# 11_VIDEO_PORT.net
KiCad netlist of a schematic drawn in Altium Designer
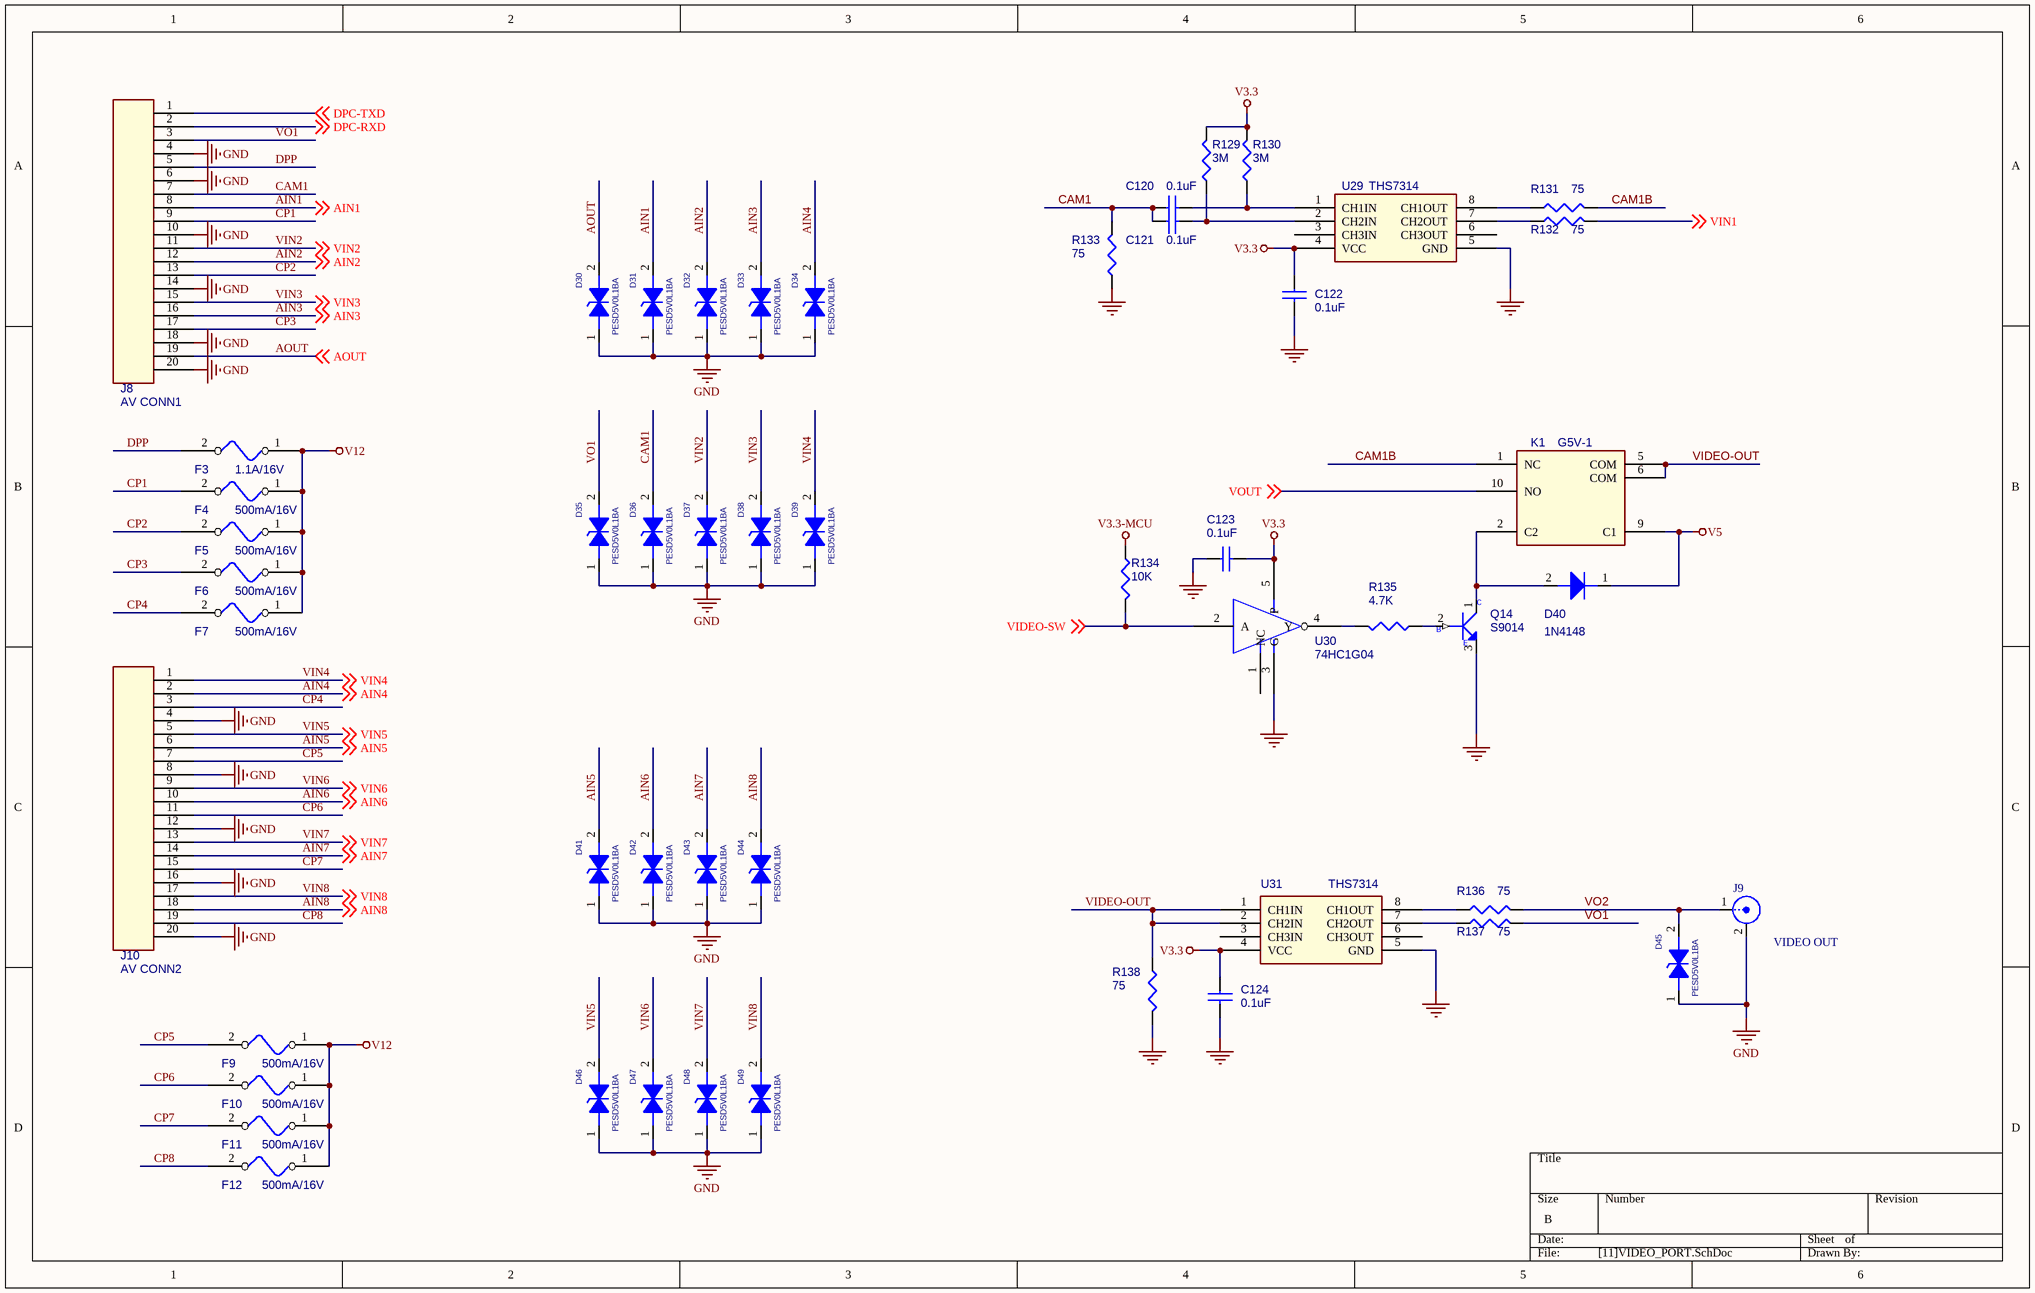
[diagram p0: [11]VIDEO_PORT.SchDoc]

(export (version "E")
  (design (tool "Eeschema 10.0.6"))
  (components
    (comp (ref "C120") (value "0.1uF") (libsource (lib "*") (part "CAP")))
    (comp (ref "C121") (value "0.1uF") (libsource (lib "*") (part "CAP")))
    (comp (ref "C122") (value "0.1uF") (libsource (lib "*") (part "CAP")))
    (comp (ref "C123")
      (value "0.1uF")
      (fields (field (name "PART NUMBER") "SE132225K8L"))
      (libsource (lib "*") (part "P_CAP NP"))
    )
    (comp (ref "C124") (value "0.1uF") (libsource (lib "*") (part "CAP")))
    (comp (ref "D30") (value "PESD5V0L1BA") (libsource (lib "*") (part "PESD")))
    (comp (ref "D31") (value "PESD5V0L1BA") (libsource (lib "*") (part "PESD")))
    (comp (ref "D32") (value "PESD5V0L1BA") (libsource (lib "*") (part "PESD")))
    (comp (ref "D33") (value "PESD5V0L1BA") (libsource (lib "*") (part "PESD")))
    (comp (ref "D34") (value "PESD5V0L1BA") (libsource (lib "*") (part "PESD")))
    (comp (ref "D35") (value "PESD5V0L1BA") (libsource (lib "*") (part "PESD")))
    (comp (ref "D36") (value "PESD5V0L1BA") (libsource (lib "*") (part "PESD")))
    (comp (ref "D37") (value "PESD5V0L1BA") (libsource (lib "*") (part "PESD")))
    (comp (ref "D38") (value "PESD5V0L1BA") (libsource (lib "*") (part "PESD")))
    (comp (ref "D39") (value "PESD5V0L1BA") (libsource (lib "*") (part "PESD")))
    (comp (ref "D40")
      (value "1N4148")
      (footprint "MINI-MELF")
      (libsource (lib "*") (part "1N4148WS-7-F_SOD323-2"))
    )
    (comp (ref "D41") (value "PESD5V0L1BA") (libsource (lib "*") (part "PESD")))
    (comp (ref "D42") (value "PESD5V0L1BA") (libsource (lib "*") (part "PESD")))
    (comp (ref "D43") (value "PESD5V0L1BA") (libsource (lib "*") (part "PESD")))
    (comp (ref "D44") (value "PESD5V0L1BA") (libsource (lib "*") (part "PESD")))
    (comp (ref "D45") (value "PESD5V0L1BA") (libsource (lib "*") (part "PESD")))
    (comp (ref "D46") (value "PESD5V0L1BA") (libsource (lib "*") (part "PESD")))
    (comp (ref "D47") (value "PESD5V0L1BA") (libsource (lib "*") (part "PESD")))
    (comp (ref "D48") (value "PESD5V0L1BA") (libsource (lib "*") (part "PESD")))
    (comp (ref "D49") (value "PESD5V0L1BA") (libsource (lib "*") (part "PESD")))
    (comp (ref "F3") (value "1.1A/16V") (libsource (lib "*") (part "2A_32VDC_0467-002")))
    (comp (ref "F4") (value "500mA/16V") (libsource (lib "*") (part "2A_32VDC_0467-002")))
    (comp (ref "F5") (value "500mA/16V") (libsource (lib "*") (part "2A_32VDC_0467-002")))
    (comp (ref "F6") (value "500mA/16V") (libsource (lib "*") (part "2A_32VDC_0467-002")))
    (comp (ref "F7") (value "500mA/16V") (libsource (lib "*") (part "2A_32VDC_0467-002")))
    (comp (ref "F9") (value "500mA/16V") (libsource (lib "*") (part "2A_32VDC_0467-002")))
    (comp (ref "F10") (value "500mA/16V") (libsource (lib "*") (part "2A_32VDC_0467-002")))
    (comp (ref "F11") (value "500mA/16V") (libsource (lib "*") (part "2A_32VDC_0467-002")))
    (comp (ref "F12") (value "500mA/16V") (libsource (lib "*") (part "2A_32VDC_0467-002")))
    (comp (ref "J8") (value "AV CONN1") (libsource (lib "*") (part "CON20")))
    (comp (ref "J9")
      (value "VIDEO OUT")
      (footprint "RCA2")
      (description "BNC Elbow Connector")
      (fields (field (name "PUBLISHER") "Altium Limited"))
      (libsource (lib "Miscellaneous Connectors") (part "BNC"))
    )
    (comp (ref "J10") (value "AV CONN2") (libsource (lib "*") (part "CON20")))
    (comp (ref "K1") (value "G5V-1") (libsource (lib "*") (part "G5V-1_0")))
    (comp (ref "Q14")
      (value "S9014")
      (footprint "NPN")
      (fields (field (name "PART NUMBER") "SB039040000"))
      (libsource (lib "*") (part "MMBT3904_NL_SOT23-3"))
    )
    (comp (ref "R129")
      (value "3M")
      (fields (field (name "PART NUMBER") "SD02810028L"))
      (libsource (lib "*") (part "R"))
    )
    (comp (ref "R130")
      (value "3M")
      (fields (field (name "PART NUMBER") "SD02810028L"))
      (libsource (lib "*") (part "R"))
    )
    (comp (ref "R131")
      (value "75")
      (fields (field (name "PART NUMBER") "SD02810028L"))
      (libsource (lib "*") (part "R"))
    )
    (comp (ref "R132")
      (value "75")
      (fields (field (name "PART NUMBER") "SD02810028L"))
      (libsource (lib "*") (part "R"))
    )
    (comp (ref "R133")
      (value "75")
      (fields (field (name "PART NUMBER") "SD02810028L"))
      (libsource (lib "*") (part "R"))
    )
    (comp (ref "R134")
      (value "10K")
      (fields (field (name "PART NUMBER") "SD02810028L"))
      (libsource (lib "*") (part "R"))
    )
    (comp (ref "R135")
      (value "4.7K")
      (fields (field (name "PART NUMBER") "SD02810028L"))
      (libsource (lib "*") (part "R"))
    )
    (comp (ref "R136")
      (value "75")
      (fields (field (name "PART NUMBER") "SD02810028L"))
      (libsource (lib "*") (part "R"))
    )
    (comp (ref "R137")
      (value "75")
      (fields (field (name "PART NUMBER") "SD02810028L"))
      (libsource (lib "*") (part "R"))
    )
    (comp (ref "R138")
      (value "75")
      (fields (field (name "PART NUMBER") "SD02810028L"))
      (libsource (lib "*") (part "R"))
    )
    (comp (ref "U29") (value "THS7314") (libsource (lib "*") (part "THS7314")))
    (comp (ref "U30") (value "74HC1G04") (libsource (lib "*") (part "74LVC1G04GW_SOT353-5")))
    (comp (ref "U31") (value "THS7314") (libsource (lib "*") (part "THS7314")))
  )
  (nets
    (net (code "1") (name "/CAM1") (class "Default")
      (node (ref "C120") (pin "1") (pinfunction "1_1") (pintype "passive"))
      (node (ref "C121") (pin "1") (pinfunction "1_1") (pintype "passive"))
      (node (ref "D36") (pin "2") (pinfunction "2_2") (pintype "passive"))
      (node (ref "J8") (pin "7") (pinfunction "7_7") (pintype "passive"))
      (node (ref "R133") (pin "2") (pinfunction "2_2") (pintype "passive"))
    )
    (net (code "2") (name "/CAM1B") (class "Default")
      (node (ref "K1") (pin "1") (pinfunction "NC_1") (pintype "passive"))
      (node (ref "R131") (pin "2") (pinfunction "2_2") (pintype "passive"))
    )
    (net (code "3") (name "/CP1") (class "Default")
      (node (ref "F4") (pin "2") (pinfunction "2_2") (pintype "passive"))
      (node (ref "J8") (pin "9") (pinfunction "9_9") (pintype "passive"))
    )
    (net (code "4") (name "/CP2") (class "Default")
      (node (ref "F5") (pin "2") (pinfunction "2_2") (pintype "passive"))
      (node (ref "J8") (pin "13") (pinfunction "13_13") (pintype "passive"))
    )
    (net (code "5") (name "/CP3") (class "Default")
      (node (ref "F6") (pin "2") (pinfunction "2_2") (pintype "passive"))
      (node (ref "J8") (pin "17") (pinfunction "17_17") (pintype "passive"))
    )
    (net (code "6") (name "/CP4") (class "Default")
      (node (ref "F7") (pin "2") (pinfunction "2_2") (pintype "passive"))
      (node (ref "J10") (pin "3") (pinfunction "3_3") (pintype "passive"))
    )
    (net (code "7") (name "/CP5") (class "Default")
      (node (ref "F9") (pin "2") (pinfunction "2_2") (pintype "passive"))
      (node (ref "J10") (pin "7") (pinfunction "7_7") (pintype "passive"))
    )
    (net (code "8") (name "/CP6") (class "Default")
      (node (ref "F10") (pin "2") (pinfunction "2_2") (pintype "passive"))
      (node (ref "J10") (pin "11") (pinfunction "11_11") (pintype "passive"))
    )
    (net (code "9") (name "/CP7") (class "Default")
      (node (ref "F11") (pin "2") (pinfunction "2_2") (pintype "passive"))
      (node (ref "J10") (pin "15") (pinfunction "15_15") (pintype "passive"))
    )
    (net (code "10") (name "/CP8") (class "Default")
      (node (ref "F12") (pin "2") (pinfunction "2_2") (pintype "passive"))
      (node (ref "J10") (pin "19") (pinfunction "19_19") (pintype "passive"))
    )
    (net (code "11") (name "/DPP") (class "Default")
      (node (ref "F3") (pin "2") (pinfunction "2_2") (pintype "passive"))
      (node (ref "J8") (pin "5") (pinfunction "5_5") (pintype "passive"))
    )
    (net (code "12") (name "/VIDEO-OUT") (class "Default")
      (node (ref "K1") (pin "5") (pinfunction "COM_5") (pintype "power_in"))
      (node (ref "K1") (pin "6") (pinfunction "COM_6") (pintype "power_in"))
      (node (ref "R138") (pin "1") (pinfunction "1_1") (pintype "passive"))
      (node (ref "U31") (pin "1") (pinfunction "CH1IN_1") (pintype "passive"))
      (node (ref "U31") (pin "2") (pinfunction "CH2IN_2") (pintype "passive"))
    )
    (net (code "13") (name "/VO1") (class "Default")
      (node (ref "D35") (pin "2") (pinfunction "2_2") (pintype "passive"))
      (node (ref "J8") (pin "3") (pinfunction "3_3") (pintype "passive"))
      (node (ref "R137") (pin "2") (pinfunction "2_2") (pintype "passive"))
    )
    (net (code "14") (name "/VO2") (class "Default")
      (node (ref "D45") (pin "2") (pinfunction "2_2") (pintype "passive"))
      (node (ref "J9") (pin "1") (pinfunction "X_1") (pintype "passive"))
      (node (ref "R136") (pin "2") (pinfunction "2_2") (pintype "passive"))
    )
    (net (code "15") (name "AIN1") (class "Default")
      (node (ref "D31") (pin "2") (pinfunction "2_2") (pintype "passive"))
      (node (ref "J8") (pin "8") (pinfunction "8_8") (pintype "passive"))
    )
    (net (code "16") (name "AIN2") (class "Default")
      (node (ref "D32") (pin "2") (pinfunction "2_2") (pintype "passive"))
      (node (ref "J8") (pin "12") (pinfunction "12_12") (pintype "passive"))
    )
    (net (code "17") (name "AIN3") (class "Default")
      (node (ref "D33") (pin "2") (pinfunction "2_2") (pintype "passive"))
      (node (ref "J8") (pin "16") (pinfunction "16_16") (pintype "passive"))
    )
    (net (code "18") (name "AIN4") (class "Default")
      (node (ref "D34") (pin "2") (pinfunction "2_2") (pintype "passive"))
      (node (ref "J10") (pin "2") (pinfunction "2_2") (pintype "passive"))
    )
    (net (code "19") (name "AIN5") (class "Default")
      (node (ref "D41") (pin "2") (pinfunction "2_2") (pintype "passive"))
      (node (ref "J10") (pin "6") (pinfunction "6_6") (pintype "passive"))
    )
    (net (code "20") (name "AIN6") (class "Default")
      (node (ref "D42") (pin "2") (pinfunction "2_2") (pintype "passive"))
      (node (ref "J10") (pin "10") (pinfunction "10_10") (pintype "passive"))
    )
    (net (code "21") (name "AIN7") (class "Default")
      (node (ref "D43") (pin "2") (pinfunction "2_2") (pintype "passive"))
      (node (ref "J10") (pin "14") (pinfunction "14_14") (pintype "passive"))
    )
    (net (code "22") (name "AIN8") (class "Default")
      (node (ref "D44") (pin "2") (pinfunction "2_2") (pintype "passive"))
      (node (ref "J10") (pin "18") (pinfunction "18_18") (pintype "passive"))
    )
    (net (code "23") (name "AOUT") (class "Default")
      (node (ref "D30") (pin "2") (pinfunction "2_2") (pintype "passive"))
      (node (ref "J8") (pin "19") (pinfunction "19_19") (pintype "passive"))
    )
    (net (code "24") (name "DPC-RXD") (class "Default")
      (node (ref "J8") (pin "2") (pinfunction "2_2") (pintype "passive"))
    )
    (net (code "25") (name "DPC-TXD") (class "Default")
      (node (ref "J8") (pin "1") (pinfunction "1_1") (pintype "passive"))
    )
    (net (code "26") (name "GND") (class "Default")
      (node (ref "C122") (pin "2") (pinfunction "2_2") (pintype "passive"))
      (node (ref "C123") (pin "1") (pinfunction "1_1") (pintype "passive"))
      (node (ref "C124") (pin "2") (pinfunction "2_2") (pintype "passive"))
      (node (ref "D30") (pin "1") (pinfunction "1_1") (pintype "passive"))
      (node (ref "D31") (pin "1") (pinfunction "1_1") (pintype "passive"))
      (node (ref "D32") (pin "1") (pinfunction "1_1") (pintype "passive"))
      (node (ref "D33") (pin "1") (pinfunction "1_1") (pintype "passive"))
      (node (ref "D34") (pin "1") (pinfunction "1_1") (pintype "passive"))
      (node (ref "D35") (pin "1") (pinfunction "1_1") (pintype "passive"))
      (node (ref "D36") (pin "1") (pinfunction "1_1") (pintype "passive"))
      (node (ref "D37") (pin "1") (pinfunction "1_1") (pintype "passive"))
      (node (ref "D38") (pin "1") (pinfunction "1_1") (pintype "passive"))
      (node (ref "D39") (pin "1") (pinfunction "1_1") (pintype "passive"))
      (node (ref "D41") (pin "1") (pinfunction "1_1") (pintype "passive"))
      (node (ref "D42") (pin "1") (pinfunction "1_1") (pintype "passive"))
      (node (ref "D43") (pin "1") (pinfunction "1_1") (pintype "passive"))
      (node (ref "D44") (pin "1") (pinfunction "1_1") (pintype "passive"))
      (node (ref "D45") (pin "1") (pinfunction "1_1") (pintype "passive"))
      (node (ref "D46") (pin "1") (pinfunction "1_1") (pintype "passive"))
      (node (ref "D47") (pin "1") (pinfunction "1_1") (pintype "passive"))
      (node (ref "D48") (pin "1") (pinfunction "1_1") (pintype "passive"))
      (node (ref "D49") (pin "1") (pinfunction "1_1") (pintype "passive"))
      (node (ref "J10") (pin "12") (pinfunction "12_12") (pintype "passive"))
      (node (ref "J10") (pin "16") (pinfunction "16_16") (pintype "passive"))
      (node (ref "J10") (pin "20") (pinfunction "20_20") (pintype "passive"))
      (node (ref "J10") (pin "4") (pinfunction "4_4") (pintype "passive"))
      (node (ref "J10") (pin "8") (pinfunction "8_8") (pintype "passive"))
      (node (ref "J8") (pin "10") (pinfunction "10_10") (pintype "passive"))
      (node (ref "J8") (pin "14") (pinfunction "14_14") (pintype "passive"))
      (node (ref "J8") (pin "18") (pinfunction "18_18") (pintype "passive"))
      (node (ref "J8") (pin "20") (pinfunction "20_20") (pintype "passive"))
      (node (ref "J8") (pin "4") (pinfunction "4_4") (pintype "passive"))
      (node (ref "J8") (pin "6") (pinfunction "6_6") (pintype "passive"))
      (node (ref "J9") (pin "2") (pinfunction "Y_2") (pintype "passive"))
      (node (ref "Q14") (pin "3") (pinfunction "EMITTER_3") (pintype "passive"))
      (node (ref "R133") (pin "1") (pinfunction "1_1") (pintype "passive"))
      (node (ref "R138") (pin "2") (pinfunction "2_2") (pintype "passive"))
      (node (ref "U29") (pin "5") (pinfunction "GND_5") (pintype "passive"))
      (node (ref "U30") (pin "3") (pinfunction "G_3") (pintype "passive"))
      (node (ref "U31") (pin "5") (pinfunction "GND_5") (pintype "passive"))
    )
    (net (code "27") (name "Net-(K1-C2)") (class "Default")
      (node (ref "D40") (pin "2") (pinfunction "2_2") (pintype "passive"))
      (node (ref "K1") (pin "2") (pinfunction "C2_2") (pintype "passive"))
      (node (ref "Q14") (pin "1") (pinfunction "COLLECTOR_1") (pintype "passive"))
    )
    (net (code "28") (name "Net-(Q14-BASE)") (class "Default")
      (node (ref "Q14") (pin "2") (pinfunction "BASE_2") (pintype "input"))
      (node (ref "R135") (pin "1") (pinfunction "1_1") (pintype "passive"))
    )
    (net (code "29") (name "Net-(U29-CH1IN)") (class "Default")
      (node (ref "C120") (pin "2") (pinfunction "2_2") (pintype "passive"))
      (node (ref "R130") (pin "1") (pinfunction "1_1") (pintype "passive"))
      (node (ref "U29") (pin "1") (pinfunction "CH1IN_1") (pintype "passive"))
    )
    (net (code "30") (name "Net-(U29-CH1OUT)") (class "Default")
      (node (ref "R131") (pin "1") (pinfunction "1_1") (pintype "passive"))
      (node (ref "U29") (pin "8") (pinfunction "CH1OUT_8") (pintype "passive"))
    )
    (net (code "31") (name "Net-(U29-CH2IN)") (class "Default")
      (node (ref "C121") (pin "2") (pinfunction "2_2") (pintype "passive"))
      (node (ref "R129") (pin "1") (pinfunction "1_1") (pintype "passive"))
      (node (ref "U29") (pin "2") (pinfunction "CH2IN_2") (pintype "passive"))
    )
    (net (code "32") (name "Net-(U29-CH2OUT)") (class "Default")
      (node (ref "R132") (pin "1") (pinfunction "1_1") (pintype "passive"))
      (node (ref "U29") (pin "7") (pinfunction "CH2OUT_7") (pintype "passive"))
    )
    (net (code "33") (name "Net-(U30-Y)") (class "Default")
      (node (ref "R135") (pin "2") (pinfunction "2_2") (pintype "passive"))
      (node (ref "U30") (pin "4") (pinfunction "Y_4") (pintype "passive"))
    )
    (net (code "34") (name "Net-(U31-CH1OUT)") (class "Default")
      (node (ref "R136") (pin "1") (pinfunction "1_1") (pintype "passive"))
      (node (ref "U31") (pin "8") (pinfunction "CH1OUT_8") (pintype "passive"))
    )
    (net (code "35") (name "Net-(U31-CH2OUT)") (class "Default")
      (node (ref "R137") (pin "1") (pinfunction "1_1") (pintype "passive"))
      (node (ref "U31") (pin "7") (pinfunction "CH2OUT_7") (pintype "passive"))
    )
    (net (code "36") (name "V3.3") (class "Default")
      (node (ref "C122") (pin "1") (pinfunction "1_1") (pintype "passive"))
      (node (ref "C123") (pin "2") (pinfunction "2_2") (pintype "passive"))
      (node (ref "C124") (pin "1") (pinfunction "1_1") (pintype "passive"))
      (node (ref "R129") (pin "2") (pinfunction "2_2") (pintype "passive"))
      (node (ref "R130") (pin "2") (pinfunction "2_2") (pintype "passive"))
      (node (ref "U29") (pin "4") (pinfunction "VCC_4") (pintype "passive"))
      (node (ref "U30") (pin "5") (pinfunction "P_5") (pintype "passive"))
      (node (ref "U31") (pin "4") (pinfunction "VCC_4") (pintype "passive"))
    )
    (net (code "37") (name "V3.3-MCU") (class "Default")
      (node (ref "R134") (pin "1") (pinfunction "1_1") (pintype "passive"))
    )
    (net (code "38") (name "V5") (class "Default")
      (node (ref "D40") (pin "1") (pinfunction "1_1") (pintype "passive"))
      (node (ref "K1") (pin "9") (pinfunction "C1_9") (pintype "passive"))
    )
    (net (code "39") (name "V12") (class "Default")
      (node (ref "F10") (pin "1") (pinfunction "1_1") (pintype "passive"))
      (node (ref "F11") (pin "1") (pinfunction "1_1") (pintype "passive"))
      (node (ref "F12") (pin "1") (pinfunction "1_1") (pintype "passive"))
      (node (ref "F3") (pin "1") (pinfunction "1_1") (pintype "passive"))
      (node (ref "F4") (pin "1") (pinfunction "1_1") (pintype "passive"))
      (node (ref "F5") (pin "1") (pinfunction "1_1") (pintype "passive"))
      (node (ref "F6") (pin "1") (pinfunction "1_1") (pintype "passive"))
      (node (ref "F7") (pin "1") (pinfunction "1_1") (pintype "passive"))
      (node (ref "F9") (pin "1") (pinfunction "1_1") (pintype "passive"))
    )
    (net (code "40") (name "VIDEO-SW") (class "Default")
      (node (ref "R134") (pin "2") (pinfunction "2_2") (pintype "passive"))
      (node (ref "U30") (pin "2") (pinfunction "A_2") (pintype "passive"))
    )
    (net (code "41") (name "VIN1") (class "Default")
      (node (ref "R132") (pin "2") (pinfunction "2_2") (pintype "passive"))
    )
    (net (code "42") (name "VIN2") (class "Default")
      (node (ref "D37") (pin "2") (pinfunction "2_2") (pintype "passive"))
      (node (ref "J8") (pin "11") (pinfunction "11_11") (pintype "passive"))
    )
    (net (code "43") (name "VIN3") (class "Default")
      (node (ref "D38") (pin "2") (pinfunction "2_2") (pintype "passive"))
      (node (ref "J8") (pin "15") (pinfunction "15_15") (pintype "passive"))
    )
    (net (code "44") (name "VIN4") (class "Default")
      (node (ref "D39") (pin "2") (pinfunction "2_2") (pintype "passive"))
      (node (ref "J10") (pin "1") (pinfunction "1_1") (pintype "passive"))
    )
    (net (code "45") (name "VIN5") (class "Default")
      (node (ref "D46") (pin "2") (pinfunction "2_2") (pintype "passive"))
      (node (ref "J10") (pin "5") (pinfunction "5_5") (pintype "passive"))
    )
    (net (code "46") (name "VIN6") (class "Default")
      (node (ref "D47") (pin "2") (pinfunction "2_2") (pintype "passive"))
      (node (ref "J10") (pin "9") (pinfunction "9_9") (pintype "passive"))
    )
    (net (code "47") (name "VIN7") (class "Default")
      (node (ref "D48") (pin "2") (pinfunction "2_2") (pintype "passive"))
      (node (ref "J10") (pin "13") (pinfunction "13_13") (pintype "passive"))
    )
    (net (code "48") (name "VIN8") (class "Default")
      (node (ref "D49") (pin "2") (pinfunction "2_2") (pintype "passive"))
      (node (ref "J10") (pin "17") (pinfunction "17_17") (pintype "passive"))
    )
    (net (code "49") (name "VOUT") (class "Default")
      (node (ref "K1") (pin "10") (pinfunction "NO_10") (pintype "passive"))
    )
    (net (code "50") (name "unconnected-(U29-CH3IN-Pad3)") (class "Default")
      (node (ref "U29") (pin "3") (pinfunction "CH3IN_3") (pintype "passive"))
    )
    (net (code "51") (name "unconnected-(U29-CH3OUT-Pad6)") (class "Default")
      (node (ref "U29") (pin "6") (pinfunction "CH3OUT_6") (pintype "passive"))
    )
    (net (code "52") (name "unconnected-(U30-NC-Pad1)") (class "Default")
      (node (ref "U30") (pin "1") (pinfunction "NC_1") (pintype "passive"))
    )
    (net (code "53") (name "unconnected-(U31-CH3IN-Pad3)") (class "Default")
      (node (ref "U31") (pin "3") (pinfunction "CH3IN_3") (pintype "passive"))
    )
    (net (code "54") (name "unconnected-(U31-CH3OUT-Pad6)") (class "Default")
      (node (ref "U31") (pin "6") (pinfunction "CH3OUT_6") (pintype "passive"))
    )
  )
)
